# analog.net
KiCad netlist of a schematic drawn in Altium Designer
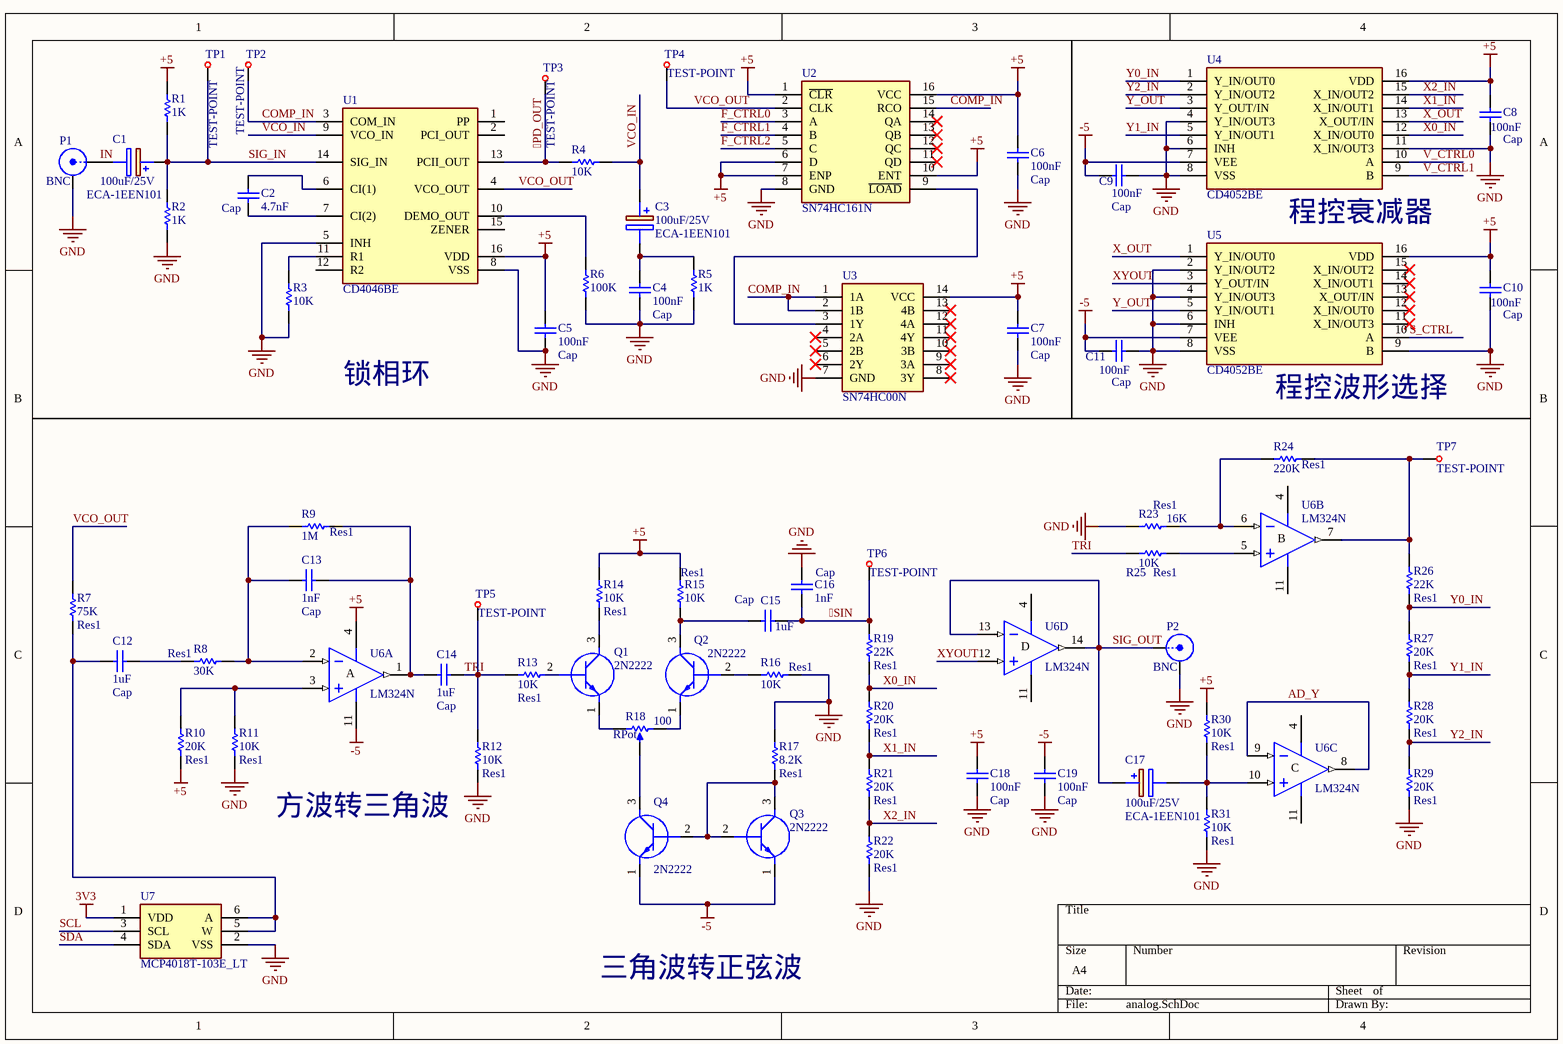
[diagram p0: analog.SchDoc]

(export (version "E")
  (design (tool "Eeschema 10.0.6"))
  (components
    (comp (ref "C1")
      (value "ECA-1EEN101")
      (footprint "CAPPRD350W65D800H1250")
      (description "Capacitor Polarised")
      (fields (field (name "MOUSER PART NUMBER") "667-ECA-1EEN101") (field (name "ALTIUM_VALUE") "100uF/25V"))
      (libsource (lib "") (part "ECA-1EEN101_2"))
    )
    (comp (ref "C2")
      (value "Cap")
      (footprint "RAD-0.2-cap")
      (description "Capacitor")
      (fields (field (name "ALTIUM_VALUE") "4.7nF") (field (name "PUBLISHER") "Altium Limited"))
      (libsource (lib "Lissajous") (part "Cap"))
    )
    (comp (ref "C3")
      (value "ECA-1EEN101")
      (footprint "CAPPRD350W65D800H1250")
      (description "Capacitor Polarised")
      (fields (field (name "MOUSER PART NUMBER") "667-ECA-1EEN101") (field (name "ALTIUM_VALUE") "100uF/25V"))
      (libsource (lib "Lissajous") (part "ECA-1EEN101"))
    )
    (comp (ref "C4")
      (value "Cap")
      (footprint "RAD-0.2-cap")
      (description "Capacitor")
      (fields (field (name "ALTIUM_VALUE") "100nF") (field (name "PUBLISHER") "Altium Limited"))
      (libsource (lib "Lissajous") (part "Cap"))
    )
    (comp (ref "C5")
      (value "Cap")
      (footprint "RAD-0.2-cap")
      (description "Capacitor")
      (fields (field (name "ALTIUM_VALUE") "100nF") (field (name "PUBLISHER") "Altium Limited"))
      (libsource (lib "Lissajous") (part "Cap"))
    )
    (comp (ref "C6")
      (value "Cap")
      (footprint "RAD-0.2-cap")
      (description "Capacitor")
      (fields (field (name "ALTIUM_VALUE") "100nF") (field (name "PUBLISHER") "Altium Limited"))
      (libsource (lib "Lissajous") (part "Cap"))
    )
    (comp (ref "C7")
      (value "Cap")
      (footprint "RAD-0.2-cap")
      (description "Capacitor")
      (fields (field (name "ALTIUM_VALUE") "100nF") (field (name "PUBLISHER") "Altium Limited"))
      (libsource (lib "Lissajous") (part "Cap"))
    )
    (comp (ref "C8")
      (value "Cap")
      (footprint "RAD-0.2-cap")
      (description "Capacitor")
      (fields (field (name "ALTIUM_VALUE") "100nF") (field (name "PUBLISHER") "Altium Limited"))
      (libsource (lib "Lissajous") (part "Cap"))
    )
    (comp (ref "C9")
      (value "Cap")
      (footprint "RAD-0.2-cap")
      (description "Capacitor")
      (fields (field (name "ALTIUM_VALUE") "100nF") (field (name "PUBLISHER") "Altium Limited"))
      (libsource (lib "Lissajous") (part "Cap"))
    )
    (comp (ref "C10")
      (value "Cap")
      (footprint "RAD-0.2-cap")
      (description "Capacitor")
      (fields (field (name "ALTIUM_VALUE") "100nF") (field (name "PUBLISHER") "Altium Limited"))
      (libsource (lib "Lissajous") (part "Cap"))
    )
    (comp (ref "C11")
      (value "Cap")
      (footprint "RAD-0.2-cap")
      (description "Capacitor")
      (fields (field (name "ALTIUM_VALUE") "100nF") (field (name "PUBLISHER") "Altium Limited"))
      (libsource (lib "Lissajous") (part "Cap"))
    )
    (comp (ref "C12")
      (value "Cap")
      (footprint "RAD-0.2-cap")
      (description "Capacitor")
      (fields (field (name "ALTIUM_VALUE") "1uF") (field (name "PUBLISHER") "Altium Limited"))
      (libsource (lib "Lissajous") (part "Cap"))
    )
    (comp (ref "C13")
      (value "Cap")
      (footprint "RAD-0.2-cap")
      (description "Capacitor")
      (fields (field (name "ALTIUM_VALUE") "1nF") (field (name "PUBLISHER") "Altium Limited"))
      (libsource (lib "Lissajous") (part "Cap"))
    )
    (comp (ref "C14")
      (value "Cap")
      (footprint "RAD-0.2-cap")
      (description "Capacitor")
      (fields (field (name "ALTIUM_VALUE") "1uF") (field (name "PUBLISHER") "Altium Limited"))
      (libsource (lib "Lissajous") (part "Cap"))
    )
    (comp (ref "C15")
      (value "Cap")
      (footprint "RAD-0.2-cap")
      (description "Capacitor")
      (fields (field (name "ALTIUM_VALUE") "1uF") (field (name "PUBLISHER") "Altium Limited"))
      (libsource (lib "Lissajous") (part "Cap"))
    )
    (comp (ref "C16")
      (value "Cap")
      (footprint "RAD-0.2-cap")
      (description "Capacitor")
      (fields (field (name "ALTIUM_VALUE") "1nF") (field (name "PUBLISHER") "Altium Limited"))
      (libsource (lib "Lissajous") (part "Cap"))
    )
    (comp (ref "C17")
      (value "ECA-1EEN101")
      (footprint "CAPPRD350W65D800H1250")
      (description "Capacitor Polarised")
      (fields (field (name "MOUSER PART NUMBER") "667-ECA-1EEN101") (field (name "ALTIUM_VALUE") "100uF/25V"))
      (libsource (lib "") (part "ECA-1EEN101_1"))
    )
    (comp (ref "C18")
      (value "Cap")
      (footprint "RAD-0.2-cap")
      (description "Capacitor")
      (fields (field (name "ALTIUM_VALUE") "100nF") (field (name "PUBLISHER") "Altium Limited"))
      (libsource (lib "Lissajous") (part "Cap"))
    )
    (comp (ref "C19")
      (value "Cap")
      (footprint "RAD-0.2-cap")
      (description "Capacitor")
      (fields (field (name "ALTIUM_VALUE") "100nF") (field (name "PUBLISHER") "Altium Limited"))
      (libsource (lib "Lissajous") (part "Cap"))
    )
    (comp (ref "P1")
      (value "BNC")
      (footprint "BNC_RA-CON")
      (description "BNC Elbow Connector")
      (fields (field (name "PUBLISHER") "Altium Limited"))
      (libsource (lib "Lissajous") (part "BNC"))
    )
    (comp (ref "P2")
      (value "BNC")
      (footprint "BNC_RA-CON")
      (description "BNC Elbow Connector")
      (fields (field (name "PUBLISHER") "Altium Limited"))
      (libsource (lib "Lissajous") (part "BNC"))
    )
    (comp (ref "Q1")
      (value "2N2222")
      (footprint "TO-92-3")
      (description "Transistor BJT NPN")
      (fields
        (field (name "MANUFACTURER_PART_NUMBER") "SS8050CTA")
        (field (name "MOUSER PART NUMBER") "512-SS8050CTA")
      )
      (libsource (lib "Lissajous") (part "2N2222"))
    )
    (comp (ref "Q2")
      (value "2N2222")
      (footprint "TO-92-3")
      (description "Transistor BJT NPN")
      (fields
        (field (name "MANUFACTURER_PART_NUMBER") "SS8050CTA")
        (field (name "MOUSER PART NUMBER") "512-SS8050CTA")
      )
      (libsource (lib "Lissajous") (part "2N2222"))
    )
    (comp (ref "Q3")
      (value "2N2222")
      (footprint "TO-92-3")
      (description "Transistor BJT NPN")
      (fields
        (field (name "MANUFACTURER_PART_NUMBER") "SS8050CTA")
        (field (name "MOUSER PART NUMBER") "512-SS8050CTA")
      )
      (libsource (lib "Lissajous") (part "2N2222"))
    )
    (comp (ref "Q4")
      (value "2N2222")
      (footprint "TO-92-3")
      (description "Transistor BJT NPN")
      (fields
        (field (name "MANUFACTURER_PART_NUMBER") "SS8050CTA")
        (field (name "MOUSER PART NUMBER") "512-SS8050CTA")
      )
      (libsource (lib "Lissajous") (part "2N2222"))
    )
    (comp (ref "R1")
      (value "1K")
      (footprint "RES-AXIAL-0.4")
      (description "Resistor")
      (fields (field (name "PUBLISHER") "Altium Limited"))
      (libsource (lib "Lissajous") (part "Res1"))
    )
    (comp (ref "R2")
      (value "1K")
      (footprint "RES-AXIAL-0.4")
      (description "Resistor")
      (fields (field (name "PUBLISHER") "Altium Limited"))
      (libsource (lib "Lissajous") (part "Res1"))
    )
    (comp (ref "R3")
      (value "10K")
      (footprint "RES-AXIAL-0.4")
      (description "Resistor")
      (fields (field (name "PUBLISHER") "Altium Limited"))
      (libsource (lib "Lissajous") (part "Res1"))
    )
    (comp (ref "R4")
      (value "10K")
      (footprint "RES-AXIAL-0.4")
      (description "Resistor")
      (fields (field (name "PUBLISHER") "Altium Limited"))
      (libsource (lib "Lissajous") (part "Res1"))
    )
    (comp (ref "R5")
      (value "1K")
      (footprint "RES-AXIAL-0.4")
      (description "Resistor")
      (fields (field (name "PUBLISHER") "Altium Limited"))
      (libsource (lib "Lissajous") (part "Res1"))
    )
    (comp (ref "R6")
      (value "100K")
      (footprint "RES-AXIAL-0.4")
      (description "Resistor")
      (fields (field (name "PUBLISHER") "Altium Limited"))
      (libsource (lib "Lissajous") (part "Res1"))
    )
    (comp (ref "R7")
      (value "Res1")
      (footprint "RES-AXIAL-0.4")
      (fields (field (name "ALTIUM_VALUE") "75K") (field (name "PUBLISHER") "Altium Limited"))
      (libsource (lib "Lissajous") (part "Res1"))
    )
    (comp (ref "R8")
      (value "Res1")
      (footprint "RES-AXIAL-0.4")
      (description "Resistor")
      (fields (field (name "ALTIUM_VALUE") "30K") (field (name "PUBLISHER") "Altium Limited"))
      (libsource (lib "Lissajous") (part "Res1"))
    )
    (comp (ref "R9")
      (value "Res1")
      (footprint "RES-AXIAL-0.4")
      (description "Resistor")
      (fields (field (name "ALTIUM_VALUE") "1M") (field (name "PUBLISHER") "Altium Limited"))
      (libsource (lib "Lissajous") (part "Res1"))
    )
    (comp (ref "R10")
      (value "Res1")
      (footprint "RES-AXIAL-0.4")
      (description "Resistor")
      (fields (field (name "ALTIUM_VALUE") "20K") (field (name "PUBLISHER") "Altium Limited"))
      (libsource (lib "Lissajous") (part "Res1"))
    )
    (comp (ref "R11")
      (value "Res1")
      (footprint "RES-AXIAL-0.4")
      (description "Resistor")
      (fields (field (name "ALTIUM_VALUE") "10K") (field (name "PUBLISHER") "Altium Limited"))
      (libsource (lib "Lissajous") (part "Res1"))
    )
    (comp (ref "R12")
      (value "Res1")
      (footprint "RES-AXIAL-0.4")
      (description "Resistor")
      (fields (field (name "ALTIUM_VALUE") "10K") (field (name "PUBLISHER") "Altium Limited"))
      (libsource (lib "Lissajous") (part "Res1"))
    )
    (comp (ref "R13")
      (value "Res1")
      (footprint "RES-AXIAL-0.4")
      (description "Resistor")
      (fields (field (name "ALTIUM_VALUE") "10K") (field (name "PUBLISHER") "Altium Limited"))
      (libsource (lib "Lissajous") (part "Res1"))
    )
    (comp (ref "R14")
      (value "Res1")
      (footprint "RES-AXIAL-0.4")
      (description "Resistor")
      (fields (field (name "ALTIUM_VALUE") "10K") (field (name "PUBLISHER") "Altium Limited"))
      (libsource (lib "Lissajous") (part "Res1"))
    )
    (comp (ref "R15")
      (value "Res1")
      (footprint "RES-AXIAL-0.4")
      (description "Resistor")
      (fields (field (name "ALTIUM_VALUE") "10K") (field (name "PUBLISHER") "Altium Limited"))
      (libsource (lib "Lissajous") (part "Res1"))
    )
    (comp (ref "R16")
      (value "Res1")
      (footprint "RES-AXIAL-0.4")
      (description "Resistor")
      (fields (field (name "ALTIUM_VALUE") "10K") (field (name "PUBLISHER") "Altium Limited"))
      (libsource (lib "Lissajous") (part "Res1"))
    )
    (comp (ref "R17")
      (value "Res1")
      (footprint "RES-AXIAL-0.4")
      (description "Resistor")
      (fields (field (name "ALTIUM_VALUE") "8.2K") (field (name "PUBLISHER") "Altium Limited"))
      (libsource (lib "Lissajous") (part "Res1"))
    )
    (comp (ref "R18")
      (value "RPot")
      (footprint "3269W")
      (description "Potentiometer")
      (fields (field (name "ALTIUM_VALUE") "100") (field (name "PUBLISHER") "Altium Limited"))
      (libsource (lib "Lissajous") (part "RPot"))
    )
    (comp (ref "R19")
      (value "Res1")
      (footprint "RES-AXIAL-0.4")
      (description "Resistor")
      (fields (field (name "ALTIUM_VALUE") "22K") (field (name "PUBLISHER") "Altium Limited"))
      (libsource (lib "Lissajous") (part "Res1"))
    )
    (comp (ref "R20")
      (value "Res1")
      (footprint "RES-AXIAL-0.4")
      (description "Resistor")
      (fields (field (name "ALTIUM_VALUE") "20K") (field (name "PUBLISHER") "Altium Limited"))
      (libsource (lib "Lissajous") (part "Res1"))
    )
    (comp (ref "R21")
      (value "Res1")
      (footprint "RES-AXIAL-0.4")
      (description "Resistor")
      (fields (field (name "ALTIUM_VALUE") "20K") (field (name "PUBLISHER") "Altium Limited"))
      (libsource (lib "Lissajous") (part "Res1"))
    )
    (comp (ref "R22")
      (value "Res1")
      (footprint "RES-AXIAL-0.4")
      (description "Resistor")
      (fields (field (name "ALTIUM_VALUE") "20K") (field (name "PUBLISHER") "Altium Limited"))
      (libsource (lib "Lissajous") (part "Res1"))
    )
    (comp (ref "R23")
      (value "Res1")
      (footprint "RES-AXIAL-0.4")
      (description "Resistor")
      (fields (field (name "ALTIUM_VALUE") "16K") (field (name "PUBLISHER") "Altium Limited"))
      (libsource (lib "Lissajous") (part "Res1"))
    )
    (comp (ref "R24")
      (value "Res1")
      (footprint "RES-AXIAL-0.4")
      (description "Resistor")
      (fields (field (name "ALTIUM_VALUE") "220K") (field (name "PUBLISHER") "Altium Limited"))
      (libsource (lib "Lissajous") (part "Res1"))
    )
    (comp (ref "R25")
      (value "Res1")
      (footprint "RES-AXIAL-0.4")
      (description "Resistor")
      (fields (field (name "ALTIUM_VALUE") "10K") (field (name "PUBLISHER") "Altium Limited"))
      (libsource (lib "Lissajous") (part "Res1"))
    )
    (comp (ref "R26")
      (value "Res1")
      (footprint "RES-AXIAL-0.4")
      (description "Resistor")
      (fields (field (name "ALTIUM_VALUE") "22K") (field (name "PUBLISHER") "Altium Limited"))
      (libsource (lib "Lissajous") (part "Res1"))
    )
    (comp (ref "R27")
      (value "Res1")
      (footprint "RES-AXIAL-0.4")
      (description "Resistor")
      (fields (field (name "ALTIUM_VALUE") "20K") (field (name "PUBLISHER") "Altium Limited"))
      (libsource (lib "Lissajous") (part "Res1"))
    )
    (comp (ref "R28")
      (value "Res1")
      (footprint "RES-AXIAL-0.4")
      (description "Resistor")
      (fields (field (name "ALTIUM_VALUE") "20K") (field (name "PUBLISHER") "Altium Limited"))
      (libsource (lib "Lissajous") (part "Res1"))
    )
    (comp (ref "R29")
      (value "Res1")
      (footprint "RES-AXIAL-0.4")
      (description "Resistor")
      (fields (field (name "ALTIUM_VALUE") "20K") (field (name "PUBLISHER") "Altium Limited"))
      (libsource (lib "Lissajous") (part "Res1"))
    )
    (comp (ref "R30")
      (value "Res1")
      (footprint "RES-AXIAL-0.4")
      (description "Resistor")
      (fields (field (name "ALTIUM_VALUE") "10K") (field (name "PUBLISHER") "Altium Limited"))
      (libsource (lib "Lissajous") (part "Res1"))
    )
    (comp (ref "R31")
      (value "Res1")
      (footprint "RES-AXIAL-0.4")
      (description "Resistor")
      (fields (field (name "ALTIUM_VALUE") "10K") (field (name "PUBLISHER") "Altium Limited"))
      (libsource (lib "Lissajous") (part "Res1"))
    )
    (comp (ref "TP1")
      (value "TEST-POINT")
      (footprint "TP")
      (description "Socket")
      (fields (field (name "PUBLISHER") "Altium Limited"))
      (libsource (lib "Lissajous") (part "TP"))
    )
    (comp (ref "TP2")
      (value "TEST-POINT")
      (footprint "TP")
      (description "Socket")
      (fields (field (name "PUBLISHER") "Altium Limited"))
      (libsource (lib "Lissajous") (part "TP"))
    )
    (comp (ref "TP3")
      (value "TEST-POINT")
      (footprint "TP")
      (description "Socket")
      (fields (field (name "PUBLISHER") "Altium Limited"))
      (libsource (lib "Lissajous") (part "TP"))
    )
    (comp (ref "TP4")
      (value "TEST-POINT")
      (footprint "TP")
      (description "Socket")
      (fields (field (name "PUBLISHER") "Altium Limited"))
      (libsource (lib "Lissajous") (part "TP"))
    )
    (comp (ref "TP5")
      (value "TEST-POINT")
      (footprint "TP")
      (description "Socket")
      (fields (field (name "PUBLISHER") "Altium Limited"))
      (libsource (lib "Lissajous") (part "TP"))
    )
    (comp (ref "TP6")
      (value "TEST-POINT")
      (footprint "TP")
      (description "Socket")
      (fields (field (name "PUBLISHER") "Altium Limited"))
      (libsource (lib "Lissajous") (part "TP"))
    )
    (comp (ref "TP7")
      (value "TEST-POINT")
      (footprint "TP")
      (description "Socket")
      (fields (field (name "PUBLISHER") "Altium Limited"))
      (libsource (lib "Lissajous") (part "TP"))
    )
    (comp (ref "U1")
      (value "CD4046BE")
      (footprint "DIP794W53P254L1930H508Q16N")
      (description "Integrated Circuit")
      (fields (field (name "MOUSER PART NUMBER") "595-CD4046BE"))
      (libsource (lib "Lissajous") (part "CD4046BE"))
    )
    (comp (ref "U2")
      (value "SN74HC161N")
      (footprint "DIP794W53P254L1930H508Q16N")
      (description "Integrated Circuit")
      (fields (field (name "MOUSER PART NUMBER") "595-SN74HC161N"))
      (libsource (lib "Lissajous") (part "SN74HC161N"))
    )
    (comp (ref "U3")
      (value "SN74HC00N")
      (footprint "DIP794W53P254L1930H508Q14N")
      (description "Integrated Circuit")
      (fields (field (name "MOUSER PART NUMBER") "595-SN74HC00N"))
      (libsource (lib "Lissajous") (part "SN74HC00N"))
    )
    (comp (ref "U4")
      (value "CD4052BE")
      (footprint "DIP794W53P254L1930H508Q16N")
      (description "Integrated Circuit")
      (fields (field (name "MOUSER PART NUMBER") "595-CD4052BE"))
      (libsource (lib "Lissajous") (part "CD4052BE"))
    )
    (comp (ref "U5")
      (value "CD4052BE")
      (footprint "DIP794W53P254L1930H508Q16N")
      (description "Integrated Circuit")
      (fields (field (name "MOUSER PART NUMBER") "595-CD4052BE"))
      (libsource (lib "Lissajous") (part "CD4052BE"))
    )
    (comp (ref "U6")
      (value "LM324N")
      (footprint "DIP794W53P254L1930H508Q14N")
      (description "Quadruple Operational Amplifier")
      (fields (field (name "PUBLISHER") "Altium Limited"))
      (libsource (lib "Lissajous") (part "LM324N"))
    )
    (comp (ref "U7")
      (value "MCP4018T-103E_LT")
      (footprint "DIP762W60P254L730H450Q6N")
      (description "Integrated Circuit")
      (fields
        (field (name "MANUFACTURER_PART_NUMBER") "MCP4018T-103E/LT")
        (field (name "MOUSER PART NUMBER") "579-MCP4018T103E/LT")
      )
      (libsource (lib "Lissajous") (part "MCP4018T-103E_LT"))
    )
  )
  (nets
    (net (code "1") (name "+5") (class "Default")
      (node (ref "C10") (pin "2") (pinfunction "2_2") (pintype "passive"))
      (node (ref "C18") (pin "2") (pinfunction "2_2") (pintype "passive"))
      (node (ref "C5") (pin "2") (pinfunction "2_2") (pintype "passive"))
      (node (ref "C6") (pin "2") (pinfunction "2_2") (pintype "passive"))
      (node (ref "C7") (pin "2") (pinfunction "2_2") (pintype "passive"))
      (node (ref "C8") (pin "2") (pinfunction "2_2") (pintype "passive"))
      (node (ref "R1") (pin "2") (pinfunction "2_2") (pintype "passive"))
      (node (ref "R10") (pin "2") (pinfunction "2_2") (pintype "passive"))
      (node (ref "R14") (pin "2") (pinfunction "2_2") (pintype "passive"))
      (node (ref "R15") (pin "2") (pinfunction "2_2") (pintype "passive"))
      (node (ref "R30") (pin "2") (pinfunction "2_2") (pintype "passive"))
      (node (ref "U1") (pin "16") (pinfunction "VDD_16") (pintype "passive"))
      (node (ref "U2") (pin "1") (pinfunction "~{CLR}_1") (pintype "passive"))
      (node (ref "U2") (pin "10") (pinfunction "ENT_10") (pintype "passive"))
      (node (ref "U2") (pin "16") (pinfunction "VCC_16") (pintype "passive"))
      (node (ref "U2") (pin "6") (pinfunction "D_6") (pintype "passive"))
      (node (ref "U2") (pin "7") (pinfunction "ENP_7") (pintype "passive"))
      (node (ref "U3") (pin "14") (pinfunction "VCC_14") (pintype "passive"))
      (node (ref "U4") (pin "16") (pinfunction "VDD_16") (pintype "passive"))
      (node (ref "U5") (pin "16") (pinfunction "VDD_16") (pintype "passive"))
      (node (ref "U6") (pin "4") (pinfunction "V+_4") (pintype "power_in"))
    )
    (net (code "2") (name "-5") (class "Default")
      (node (ref "C11") (pin "2") (pinfunction "2_2") (pintype "passive"))
      (node (ref "C19") (pin "2") (pinfunction "2_2") (pintype "passive"))
      (node (ref "C9") (pin "1") (pinfunction "1_1") (pintype "passive"))
      (node (ref "Q3") (pin "1") (pinfunction "E_1") (pintype "passive"))
      (node (ref "Q4") (pin "1") (pinfunction "E_1") (pintype "passive"))
      (node (ref "U4") (pin "7") (pinfunction "VEE_7") (pintype "passive"))
      (node (ref "U5") (pin "7") (pinfunction "VEE_7") (pintype "passive"))
      (node (ref "U6") (pin "11") (pinfunction "V-_11") (pintype "power_in"))
    )
    (net (code "3") (name "/PD_OUT") (class "Default")
      (node (ref "R4") (pin "2") (pinfunction "2_2") (pintype "passive"))
      (node (ref "TP3") (pin "1") (pinfunction "1_1") (pintype "passive"))
      (node (ref "U1") (pin "13") (pinfunction "PCII_OUT_13") (pintype "passive"))
    )
    (net (code "4") (name "/SIN") (class "Default")
      (node (ref "C15") (pin "2") (pinfunction "2_2") (pintype "passive"))
      (node (ref "C16") (pin "1") (pinfunction "1_1") (pintype "passive"))
      (node (ref "R19") (pin "2") (pinfunction "2_2") (pintype "passive"))
      (node (ref "TP6") (pin "1") (pinfunction "1_1") (pintype "passive"))
    )
    (net (code "5") (name "/AD_Y") (class "Default")
      (node (ref "U6") (pin "8") (pinfunction "OUT_8") (pintype "output"))
      (node (ref "U6") (pin "9") (pinfunction "IN-_9") (pintype "input"))
    )
    (net (code "6") (name "/COMP_IN") (class "Default")
      (node (ref "TP2") (pin "1") (pinfunction "1_1") (pintype "passive"))
      (node (ref "U1") (pin "3") (pinfunction "COM_IN_3") (pintype "passive"))
      (node (ref "U2") (pin "15") (pinfunction "RCO_15") (pintype "passive"))
      (node (ref "U3") (pin "1") (pinfunction "1A_1") (pintype "passive"))
      (node (ref "U3") (pin "2") (pinfunction "1B_2") (pintype "passive"))
    )
    (net (code "7") (name "/F_CTRL0") (class "Default")
      (node (ref "U2") (pin "3") (pinfunction "A_3") (pintype "passive"))
    )
    (net (code "8") (name "/F_CTRL1") (class "Default")
      (node (ref "U2") (pin "4") (pinfunction "B_4") (pintype "passive"))
    )
    (net (code "9") (name "/F_CTRL2") (class "Default")
      (node (ref "U2") (pin "5") (pinfunction "C_5") (pintype "passive"))
    )
    (net (code "10") (name "/IN") (class "Default")
      (node (ref "C1") (pin "2") (pinfunction "-_2") (pintype "passive"))
      (node (ref "P1") (pin "1") (pinfunction "X_1") (pintype "passive"))
    )
    (net (code "11") (name "/SCL") (class "Default")
      (node (ref "U7") (pin "3") (pinfunction "SCL_3") (pintype "passive"))
    )
    (net (code "12") (name "/SDA") (class "Default")
      (node (ref "U7") (pin "4") (pinfunction "SDA_4") (pintype "passive"))
    )
    (net (code "13") (name "/SIG_IN") (class "Default")
      (node (ref "C1") (pin "1") (pinfunction "+_1") (pintype "passive"))
      (node (ref "R1") (pin "1") (pinfunction "1_1") (pintype "passive"))
      (node (ref "R2") (pin "2") (pinfunction "2_2") (pintype "passive"))
      (node (ref "TP1") (pin "1") (pinfunction "1_1") (pintype "passive"))
      (node (ref "U1") (pin "14") (pinfunction "SIG_IN_14") (pintype "passive"))
    )
    (net (code "14") (name "/SIG_OUT") (class "Default")
      (node (ref "C17") (pin "1") (pinfunction "+_1") (pintype "passive"))
      (node (ref "P2") (pin "1") (pinfunction "X_1") (pintype "passive"))
      (node (ref "U6") (pin "13") (pinfunction "IN-_13") (pintype "input"))
      (node (ref "U6") (pin "14") (pinfunction "OUT_14") (pintype "output"))
    )
    (net (code "15") (name "/S_CTRL") (class "Default")
      (node (ref "U5") (pin "10") (pinfunction "A_10") (pintype "passive"))
    )
    (net (code "16") (name "/TRI") (class "Default")
      (node (ref "C14") (pin "2") (pinfunction "2_2") (pintype "passive"))
      (node (ref "R12") (pin "1") (pinfunction "1_1") (pintype "passive"))
      (node (ref "R13") (pin "1") (pinfunction "1_1") (pintype "passive"))
      (node (ref "R25") (pin "2") (pinfunction "2_2") (pintype "passive"))
      (node (ref "TP5") (pin "1") (pinfunction "1_1") (pintype "passive"))
    )
    (net (code "17") (name "/VCO_IN") (class "Default")
      (node (ref "C3") (pin "1") (pinfunction "+_1") (pintype "passive"))
      (node (ref "R4") (pin "1") (pinfunction "1_1") (pintype "passive"))
      (node (ref "U1") (pin "9") (pinfunction "VCO_IN_9") (pintype "passive"))
    )
    (net (code "18") (name "/VCO_OUT") (class "Default")
      (node (ref "R7") (pin "2") (pinfunction "2_2") (pintype "passive"))
      (node (ref "TP4") (pin "1") (pinfunction "1_1") (pintype "passive"))
      (node (ref "U1") (pin "4") (pinfunction "VCO_OUT_4") (pintype "passive"))
      (node (ref "U2") (pin "2") (pinfunction "CLK_2") (pintype "passive"))
    )
    (net (code "19") (name "/V_CTRL0") (class "Default")
      (node (ref "U4") (pin "10") (pinfunction "A_10") (pintype "passive"))
    )
    (net (code "20") (name "/V_CTRL1") (class "Default")
      (node (ref "U4") (pin "9") (pinfunction "B_9") (pintype "passive"))
    )
    (net (code "21") (name "/X0_IN") (class "Default")
      (node (ref "R19") (pin "1") (pinfunction "1_1") (pintype "passive"))
      (node (ref "R20") (pin "2") (pinfunction "2_2") (pintype "passive"))
      (node (ref "U4") (pin "12") (pinfunction "X_IN/OUT0_12") (pintype "passive"))
    )
    (net (code "22") (name "/X1_IN") (class "Default")
      (node (ref "R20") (pin "1") (pinfunction "1_1") (pintype "passive"))
      (node (ref "R21") (pin "2") (pinfunction "2_2") (pintype "passive"))
      (node (ref "U4") (pin "14") (pinfunction "X_IN/OUT1_14") (pintype "passive"))
    )
    (net (code "23") (name "/X2_IN") (class "Default")
      (node (ref "R21") (pin "1") (pinfunction "1_1") (pintype "passive"))
      (node (ref "R22") (pin "2") (pinfunction "2_2") (pintype "passive"))
      (node (ref "U4") (pin "15") (pinfunction "X_IN/OUT2_15") (pintype "passive"))
    )
    (net (code "24") (name "/XYOUT") (class "Default")
      (node (ref "U5") (pin "3") (pinfunction "Y_OUT/IN_3") (pintype "passive"))
      (node (ref "U6") (pin "12") (pinfunction "IN+_12") (pintype "input"))
    )
    (net (code "25") (name "/X_OUT") (class "Default")
      (node (ref "U4") (pin "13") (pinfunction "X_OUT/IN_13") (pintype "passive"))
      (node (ref "U5") (pin "1") (pinfunction "Y_IN/OUT0_1") (pintype "passive"))
    )
    (net (code "26") (name "/Y0_IN") (class "Default")
      (node (ref "R26") (pin "1") (pinfunction "1_1") (pintype "passive"))
      (node (ref "R27") (pin "2") (pinfunction "2_2") (pintype "passive"))
      (node (ref "U4") (pin "1") (pinfunction "Y_IN/OUT0_1") (pintype "passive"))
    )
    (net (code "27") (name "/Y1_IN") (class "Default")
      (node (ref "R27") (pin "1") (pinfunction "1_1") (pintype "passive"))
      (node (ref "R28") (pin "2") (pinfunction "2_2") (pintype "passive"))
      (node (ref "U4") (pin "5") (pinfunction "Y_IN/OUT1_5") (pintype "passive"))
    )
    (net (code "28") (name "/Y2_IN") (class "Default")
      (node (ref "R28") (pin "1") (pinfunction "1_1") (pintype "passive"))
      (node (ref "R29") (pin "2") (pinfunction "2_2") (pintype "passive"))
      (node (ref "U4") (pin "2") (pinfunction "Y_IN/OUT2_2") (pintype "passive"))
    )
    (net (code "29") (name "/Y_OUT") (class "Default")
      (node (ref "U4") (pin "3") (pinfunction "Y_OUT/IN_3") (pintype "passive"))
      (node (ref "U5") (pin "5") (pinfunction "Y_IN/OUT1_5") (pintype "passive"))
    )
    (net (code "30") (name "3V3") (class "Default")
      (node (ref "U7") (pin "1") (pinfunction "VDD_1") (pintype "passive"))
    )
    (net (code "31") (name "GND") (class "Default")
      (node (ref "C10") (pin "1") (pinfunction "1_1") (pintype "passive"))
      (node (ref "C11") (pin "1") (pinfunction "1_1") (pintype "passive"))
      (node (ref "C16") (pin "2") (pinfunction "2_2") (pintype "passive"))
      (node (ref "C18") (pin "1") (pinfunction "1_1") (pintype "passive"))
      (node (ref "C19") (pin "1") (pinfunction "1_1") (pintype "passive"))
      (node (ref "C4") (pin "1") (pinfunction "1_1") (pintype "passive"))
      (node (ref "C5") (pin "1") (pinfunction "1_1") (pintype "passive"))
      (node (ref "C6") (pin "1") (pinfunction "1_1") (pintype "passive"))
      (node (ref "C7") (pin "1") (pinfunction "1_1") (pintype "passive"))
      (node (ref "C8") (pin "1") (pinfunction "1_1") (pintype "passive"))
      (node (ref "C9") (pin "2") (pinfunction "2_2") (pintype "passive"))
      (node (ref "P1") (pin "2") (pinfunction "Y_2") (pintype "passive"))
      (node (ref "P2") (pin "2") (pinfunction "Y_2") (pintype "passive"))
      (node (ref "R11") (pin "2") (pinfunction "2_2") (pintype "passive"))
      (node (ref "R12") (pin "2") (pinfunction "2_2") (pintype "passive"))
      (node (ref "R16") (pin "1") (pinfunction "1_1") (pintype "passive"))
      (node (ref "R17") (pin "1") (pinfunction "1_1") (pintype "passive"))
      (node (ref "R2") (pin "1") (pinfunction "1_1") (pintype "passive"))
      (node (ref "R22") (pin "1") (pinfunction "1_1") (pintype "passive"))
      (node (ref "R23") (pin "2") (pinfunction "2_2") (pintype "passive"))
      (node (ref "R29") (pin "1") (pinfunction "1_1") (pintype "passive"))
      (node (ref "R3") (pin "1") (pinfunction "1_1") (pintype "passive"))
      (node (ref "R31") (pin "1") (pinfunction "1_1") (pintype "passive"))
      (node (ref "R5") (pin "1") (pinfunction "1_1") (pintype "passive"))
      (node (ref "R6") (pin "1") (pinfunction "1_1") (pintype "passive"))
      (node (ref "U1") (pin "5") (pinfunction "INH_5") (pintype "passive"))
      (node (ref "U1") (pin "8") (pinfunction "VSS_8") (pintype "passive"))
      (node (ref "U2") (pin "8") (pinfunction "GND_8") (pintype "passive"))
      (node (ref "U3") (pin "7") (pinfunction "GND_7") (pintype "passive"))
      (node (ref "U4") (pin "11") (pinfunction "X_IN/OUT3_11") (pintype "passive"))
      (node (ref "U4") (pin "4") (pinfunction "Y_IN/OUT3_4") (pintype "passive"))
      (node (ref "U4") (pin "6") (pinfunction "INH_6") (pintype "passive"))
      (node (ref "U4") (pin "8") (pinfunction "VSS_8") (pintype "passive"))
      (node (ref "U5") (pin "2") (pinfunction "Y_IN/OUT2_2") (pintype "passive"))
      (node (ref "U5") (pin "4") (pinfunction "Y_IN/OUT3_4") (pintype "passive"))
      (node (ref "U5") (pin "6") (pinfunction "INH_6") (pintype "passive"))
      (node (ref "U5") (pin "8") (pinfunction "VSS_8") (pintype "passive"))
      (node (ref "U5") (pin "9") (pinfunction "B_9") (pintype "passive"))
      (node (ref "U7") (pin "2") (pinfunction "VSS_2") (pintype "passive"))
    )
    (net (code "32") (name "Net-(C3--)") (class "Default")
      (node (ref "C3") (pin "2") (pinfunction "-_2") (pintype "passive"))
      (node (ref "C4") (pin "2") (pinfunction "2_2") (pintype "passive"))
      (node (ref "R5") (pin "2") (pinfunction "2_2") (pintype "passive"))
    )
    (net (code "33") (name "Net-(C12-Pad2)") (class "Default")
      (node (ref "C12") (pin "2") (pinfunction "2_2") (pintype "passive"))
      (node (ref "R8") (pin "2") (pinfunction "2_2") (pintype "passive"))
    )
    (net (code "34") (name "Net-(C17--)") (class "Default")
      (node (ref "C17") (pin "2") (pinfunction "-_2") (pintype "passive"))
      (node (ref "R30") (pin "1") (pinfunction "1_1") (pintype "passive"))
      (node (ref "R31") (pin "2") (pinfunction "2_2") (pintype "passive"))
      (node (ref "U6") (pin "10") (pinfunction "IN+_10") (pintype "input"))
    )
    (net (code "35") (name "Net-(Q1-B)") (class "Default")
      (node (ref "Q1") (pin "2") (pinfunction "B_2") (pintype "passive"))
      (node (ref "R13") (pin "2") (pinfunction "2_2") (pintype "passive"))
    )
    (net (code "36") (name "Net-(Q1-C)") (class "Default")
      (node (ref "Q1") (pin "3") (pinfunction "C_3") (pintype "passive"))
      (node (ref "R14") (pin "1") (pinfunction "1_1") (pintype "passive"))
    )
    (net (code "37") (name "Net-(Q1-E)") (class "Default")
      (node (ref "Q1") (pin "1") (pinfunction "E_1") (pintype "passive"))
      (node (ref "R18") (pin "1") (pinfunction "TOP_1") (pintype "passive"))
    )
    (net (code "38") (name "Net-(Q2-B)") (class "Default")
      (node (ref "Q2") (pin "2") (pinfunction "B_2") (pintype "passive"))
      (node (ref "R16") (pin "2") (pinfunction "2_2") (pintype "passive"))
    )
    (net (code "39") (name "Net-(Q2-C)") (class "Default")
      (node (ref "C15") (pin "1") (pinfunction "1_1") (pintype "passive"))
      (node (ref "Q2") (pin "3") (pinfunction "C_3") (pintype "passive"))
      (node (ref "R15") (pin "1") (pinfunction "1_1") (pintype "passive"))
    )
    (net (code "40") (name "Net-(Q2-E)") (class "Default")
      (node (ref "Q2") (pin "1") (pinfunction "E_1") (pintype "passive"))
      (node (ref "R18") (pin "3") (pinfunction "BOT_3") (pintype "passive"))
    )
    (net (code "41") (name "Net-(Q3-B)") (class "Default")
      (node (ref "Q3") (pin "2") (pinfunction "B_2") (pintype "passive"))
      (node (ref "Q3") (pin "3") (pinfunction "C_3") (pintype "passive"))
      (node (ref "Q4") (pin "2") (pinfunction "B_2") (pintype "passive"))
      (node (ref "R17") (pin "2") (pinfunction "2_2") (pintype "passive"))
    )
    (net (code "42") (name "Net-(Q4-C)") (class "Default")
      (node (ref "Q4") (pin "3") (pinfunction "C_3") (pintype "passive"))
      (node (ref "R18") (pin "2") (pinfunction "TAP_2") (pintype "passive"))
    )
    (net (code "43") (name "Net-(U1-CI(1))") (class "Default")
      (node (ref "C2") (pin "2") (pinfunction "2_2") (pintype "passive"))
      (node (ref "U1") (pin "6") (pinfunction "CI(1)_6") (pintype "passive"))
    )
    (net (code "44") (name "Net-(U1-CI(2))") (class "Default")
      (node (ref "C2") (pin "1") (pinfunction "1_1") (pintype "passive"))
      (node (ref "U1") (pin "7") (pinfunction "CI(2)_7") (pintype "passive"))
    )
    (net (code "45") (name "Net-(U1-DEMO_OUT)") (class "Default")
      (node (ref "R6") (pin "2") (pinfunction "2_2") (pintype "passive"))
      (node (ref "U1") (pin "10") (pinfunction "DEMO_OUT_10") (pintype "passive"))
    )
    (net (code "46") (name "Net-(U1-R1)") (class "Default")
      (node (ref "R3") (pin "2") (pinfunction "2_2") (pintype "passive"))
      (node (ref "U1") (pin "11") (pinfunction "R1_11") (pintype "passive"))
    )
    (net (code "47") (name "Net-(U2-~{LOAD})") (class "Default")
      (node (ref "U2") (pin "9") (pinfunction "~{LOAD}_9") (pintype "passive"))
      (node (ref "U3") (pin "3") (pinfunction "1Y_3") (pintype "passive"))
    )
    (net (code "48") (name "Net-(U6A-IN+)") (class "Default")
      (node (ref "R10") (pin "1") (pinfunction "1_1") (pintype "passive"))
      (node (ref "R11") (pin "1") (pinfunction "1_1") (pintype "passive"))
      (node (ref "U6") (pin "3") (pinfunction "IN+_3") (pintype "input"))
    )
    (net (code "49") (name "Net-(U6A-IN-)") (class "Default")
      (node (ref "C13") (pin "1") (pinfunction "1_1") (pintype "passive"))
      (node (ref "R8") (pin "1") (pinfunction "1_1") (pintype "passive"))
      (node (ref "R9") (pin "2") (pinfunction "2_2") (pintype "passive"))
      (node (ref "U6") (pin "2") (pinfunction "IN-_2") (pintype "input"))
    )
    (net (code "50") (name "Net-(U6A-OUT)") (class "Default")
      (node (ref "C13") (pin "2") (pinfunction "2_2") (pintype "passive"))
      (node (ref "C14") (pin "1") (pinfunction "1_1") (pintype "passive"))
      (node (ref "R9") (pin "1") (pinfunction "1_1") (pintype "passive"))
      (node (ref "U6") (pin "1") (pinfunction "OUT_1") (pintype "output"))
    )
    (net (code "51") (name "Net-(U6B-IN+)") (class "Default")
      (node (ref "R25") (pin "1") (pinfunction "1_1") (pintype "passive"))
      (node (ref "U6") (pin "5") (pinfunction "IN+_5") (pintype "input"))
    )
    (net (code "52") (name "Net-(U6B-IN-)") (class "Default")
      (node (ref "R23") (pin "1") (pinfunction "1_1") (pintype "passive"))
      (node (ref "R24") (pin "1") (pinfunction "1_1") (pintype "passive"))
      (node (ref "U6") (pin "6") (pinfunction "IN-_6") (pintype "input"))
    )
    (net (code "53") (name "Net-(U6B-OUT)") (class "Default")
      (node (ref "R24") (pin "2") (pinfunction "2_2") (pintype "passive"))
      (node (ref "R26") (pin "2") (pinfunction "2_2") (pintype "passive"))
      (node (ref "TP7") (pin "1") (pinfunction "1_1") (pintype "passive"))
      (node (ref "U6") (pin "7") (pinfunction "OUT_7") (pintype "output"))
    )
    (net (code "54") (name "Net-(U7-A)") (class "Default")
      (node (ref "C12") (pin "1") (pinfunction "1_1") (pintype "passive"))
      (node (ref "R7") (pin "1") (pinfunction "1_1") (pintype "passive"))
      (node (ref "U7") (pin "5") (pinfunction "W_5") (pintype "passive"))
      (node (ref "U7") (pin "6") (pinfunction "A_6") (pintype "passive"))
    )
    (net (code "55") (name "unconnected-(U1-PCI_OUT-Pad2)") (class "Default")
      (node (ref "U1") (pin "2") (pinfunction "PCI_OUT_2") (pintype "passive"))
    )
    (net (code "56") (name "unconnected-(U1-PP-Pad1)") (class "Default")
      (node (ref "U1") (pin "1") (pinfunction "PP_1") (pintype "passive"))
    )
    (net (code "57") (name "unconnected-(U1-R2-Pad12)") (class "Default")
      (node (ref "U1") (pin "12") (pinfunction "R2_12") (pintype "passive"))
    )
    (net (code "58") (name "unconnected-(U1-ZENER-Pad15)") (class "Default")
      (node (ref "U1") (pin "15") (pinfunction "ZENER_15") (pintype "passive"))
    )
    (net (code "59") (name "unconnected-(U2-QA-Pad14)") (class "Default")
      (node (ref "U2") (pin "14") (pinfunction "QA_14") (pintype "passive+no_connect"))
    )
    (net (code "60") (name "unconnected-(U2-QB-Pad13)") (class "Default")
      (node (ref "U2") (pin "13") (pinfunction "QB_13") (pintype "passive+no_connect"))
    )
    (net (code "61") (name "unconnected-(U2-QC-Pad12)") (class "Default")
      (node (ref "U2") (pin "12") (pinfunction "QC_12") (pintype "passive+no_connect"))
    )
    (net (code "62") (name "unconnected-(U2-QD-Pad11)") (class "Default")
      (node (ref "U2") (pin "11") (pinfunction "QD_11") (pintype "passive+no_connect"))
    )
    (net (code "63") (name "unconnected-(U3-2A-Pad4)") (class "Default")
      (node (ref "U3") (pin "4") (pinfunction "2A_4") (pintype "passive+no_connect"))
    )
    (net (code "64") (name "unconnected-(U3-2B-Pad5)") (class "Default")
      (node (ref "U3") (pin "5") (pinfunction "2B_5") (pintype "passive+no_connect"))
    )
    (net (code "65") (name "unconnected-(U3-2Y-Pad6)") (class "Default")
      (node (ref "U3") (pin "6") (pinfunction "2Y_6") (pintype "passive+no_connect"))
    )
    (net (code "66") (name "unconnected-(U3-3A-Pad9)") (class "Default")
      (node (ref "U3") (pin "9") (pinfunction "3A_9") (pintype "passive+no_connect"))
    )
    (net (code "67") (name "unconnected-(U3-3B-Pad10)") (class "Default")
      (node (ref "U3") (pin "10") (pinfunction "3B_10") (pintype "passive+no_connect"))
    )
    (net (code "68") (name "unconnected-(U3-3Y-Pad8)") (class "Default")
      (node (ref "U3") (pin "8") (pinfunction "3Y_8") (pintype "passive+no_connect"))
    )
    (net (code "69") (name "unconnected-(U3-4A-Pad12)") (class "Default")
      (node (ref "U3") (pin "12") (pinfunction "4A_12") (pintype "passive+no_connect"))
    )
    (net (code "70") (name "unconnected-(U3-4B-Pad13)") (class "Default")
      (node (ref "U3") (pin "13") (pinfunction "4B_13") (pintype "passive+no_connect"))
    )
    (net (code "71") (name "unconnected-(U3-4Y-Pad11)") (class "Default")
      (node (ref "U3") (pin "11") (pinfunction "4Y_11") (pintype "passive+no_connect"))
    )
    (net (code "72") (name "unconnected-(U5-X_IN{slash}OUT0-Pad12)") (class "Default")
      (node (ref "U5") (pin "12") (pinfunction "X_IN/OUT0_12") (pintype "passive+no_connect"))
    )
    (net (code "73") (name "unconnected-(U5-X_IN{slash}OUT1-Pad14)") (class "Default")
      (node (ref "U5") (pin "14") (pinfunction "X_IN/OUT1_14") (pintype "passive+no_connect"))
    )
    (net (code "74") (name "unconnected-(U5-X_IN{slash}OUT2-Pad15)") (class "Default")
      (node (ref "U5") (pin "15") (pinfunction "X_IN/OUT2_15") (pintype "passive+no_connect"))
    )
    (net (code "75") (name "unconnected-(U5-X_IN{slash}OUT3-Pad11)") (class "Default")
      (node (ref "U5") (pin "11") (pinfunction "X_IN/OUT3_11") (pintype "passive+no_connect"))
    )
    (net (code "76") (name "unconnected-(U5-X_OUT{slash}IN-Pad13)") (class "Default")
      (node (ref "U5") (pin "13") (pinfunction "X_OUT/IN_13") (pintype "passive+no_connect"))
    )
    (net (code "77") (name "unconnected-(U6B-V+-Pad4)") (class "Default")
      (node (ref "U6") (pin "4") (pinfunction "V+_4") (pintype "power_in"))
    )
    (net (code "78") (name "unconnected-(U6B-V--Pad11)") (class "Default")
      (node (ref "U6") (pin "11") (pinfunction "V-_11") (pintype "power_in"))
    )
    (net (code "79") (name "unconnected-(U6C-V+-Pad4)") (class "Default")
      (node (ref "U6") (pin "4") (pinfunction "V+_4") (pintype "power_in"))
    )
    (net (code "80") (name "unconnected-(U6C-V--Pad11)") (class "Default")
      (node (ref "U6") (pin "11") (pinfunction "V-_11") (pintype "power_in"))
    )
    (net (code "81") (name "unconnected-(U6D-V+-Pad4)") (class "Default")
      (node (ref "U6") (pin "4") (pinfunction "V+_4") (pintype "power_in"))
    )
    (net (code "82") (name "unconnected-(U6D-V--Pad11)") (class "Default")
      (node (ref "U6") (pin "11") (pinfunction "V-_11") (pintype "power_in"))
    )
  )
)
